# subway-timetable.net
KiCad netlist of a schematic drawn in EAGLE
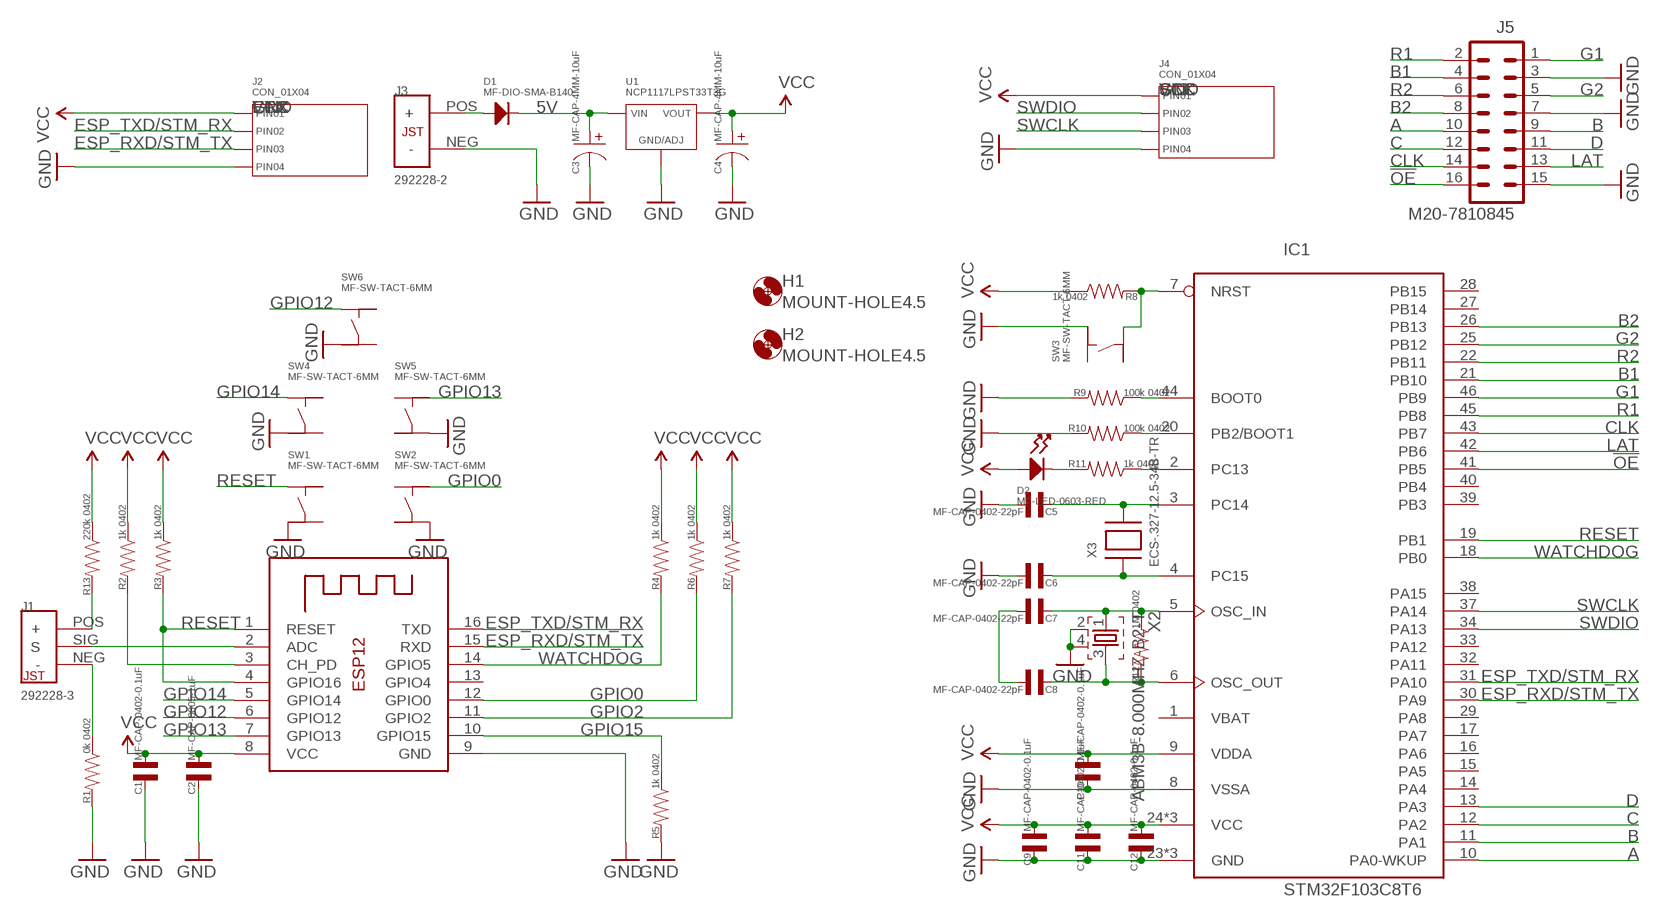
[diagram p0: schematic, sheet 1]

(export (version "E")
  (design (tool "Eeschema 10.0.6"))
  (components
    (comp (ref "C1")
      (value "MF-CAP-0402-0.1uF")
      (footprint "eagle-import:C0402")
      (libsource (lib "eagle-import") (part "CAPACITOR_NP_0402"))
    )
    (comp (ref "C2")
      (value "MF-CAP-0805-1uF")
      (footprint "eagle-import:C0805")
      (libsource (lib "eagle-import") (part "CAPACITOR_NP_0805"))
    )
    (comp (ref "C3")
      (value "MF-CAP-4MM-10uF")
      (footprint "eagle-import:CP4MM")
      (libsource (lib "eagle-import") (part "CAPACITOR_P_4MM"))
    )
    (comp (ref "C4")
      (value "MF-CAP-4MM-10uF")
      (footprint "eagle-import:CP4MM")
      (libsource (lib "eagle-import") (part "CAPACITOR_P_4MM"))
    )
    (comp (ref "C5")
      (value "MF-CAP-0402-22pF")
      (footprint "eagle-import:C0402")
      (libsource (lib "eagle-import") (part "CAPACITOR_NP_0402"))
    )
    (comp (ref "C6")
      (value "MF-CAP-0402-22pF")
      (footprint "eagle-import:C0402")
      (libsource (lib "eagle-import") (part "CAPACITOR_NP_0402"))
    )
    (comp (ref "C7")
      (value "MF-CAP-0402-22pF")
      (footprint "eagle-import:C0402")
      (libsource (lib "eagle-import") (part "CAPACITOR_NP_0402"))
    )
    (comp (ref "C8")
      (value "MF-CAP-0402-22pF")
      (footprint "eagle-import:C0402")
      (libsource (lib "eagle-import") (part "CAPACITOR_NP_0402"))
    )
    (comp (ref "C9")
      (value "MF-CAP-0402-0.1uF")
      (footprint "eagle-import:C0402")
      (libsource (lib "eagle-import") (part "CAPACITOR_NP_0402"))
    )
    (comp (ref "C10")
      (value "MF-CAP-0402-0.1uF")
      (footprint "eagle-import:C0402")
      (libsource (lib "eagle-import") (part "CAPACITOR_NP_0402"))
    )
    (comp (ref "C11")
      (value "MF-CAP-0402-0.1uF")
      (footprint "eagle-import:C0402")
      (libsource (lib "eagle-import") (part "CAPACITOR_NP_0402"))
    )
    (comp (ref "C12")
      (value "MF-CAP-0402-0.1uF")
      (footprint "eagle-import:C0402")
      (libsource (lib "eagle-import") (part "CAPACITOR_NP_0402"))
    )
    (comp (ref "D1")
      (value "MF-DIO-SMA-B140")
      (footprint "eagle-import:SMA")
      (fields (field (name "HOUSEPART") "YES"))
      (libsource (lib "eagle-import") (part "DIODES_SMA_B140"))
    )
    (comp (ref "D2")
      (value "MF-LED-0603-RED")
      (footprint "eagle-import:LED0603")
      (fields (field (name "HOUSEPART") "YES"))
      (libsource (lib "eagle-import") (part "LED_SINGLE-0603-RED"))
    )
    (comp (ref "H1")
      (value "MOUNT-HOLE4.5")
      (footprint "eagle-import:4,5")
      (libsource (lib "eagle-import") (part "MOUNT-HOLE4.5"))
    )
    (comp (ref "H2")
      (value "MOUNT-HOLE4.5")
      (footprint "eagle-import:4,5")
      (libsource (lib "eagle-import") (part "MOUNT-HOLE4.5"))
    )
    (comp (ref "IC1")
      (value "STM32F103C8T6")
      (footprint "eagle-import:LQFP48")
      (libsource (lib "eagle-import") (part "STM32F103CT8"))
    )
    (comp (ref "J1")
      (value "292228-3")
      (footprint "eagle-import:292228-3")
      (libsource (lib "eagle-import") (part "MINICT-3"))
    )
    (comp (ref "J2")
      (value "CON_01X04")
      (footprint "eagle-import:PTH_2.54MM_01X04_SPECIAL")
      (fields
        (field (name "LABEL01") "VCC")
        (field (name "LABEL02") "ETX")
        (field (name "LABEL03") "ERX")
        (field (name "LABEL04") "GND")
      )
      (libsource (lib "eagle-import") (part "CON_01X04"))
    )
    (comp (ref "J3")
      (value "292228-2")
      (footprint "eagle-import:292228-2")
      (libsource (lib "eagle-import") (part "MINICT"))
    )
    (comp (ref "J4")
      (value "CON_01X04")
      (footprint "eagle-import:PTH_2.54MM_01X04_SPECIAL")
      (fields
        (field (name "LABEL01") "VCC")
        (field (name "LABEL02") "SIO")
        (field (name "LABEL03") "SCK")
        (field (name "LABEL04") "GND")
      )
      (libsource (lib "eagle-import") (part "CON_01X04"))
    )
    (comp (ref "J5")
      (value "M20-7810845")
      (footprint "eagle-import:2X8_SMD")
      (libsource (lib "eagle-import") (part "M08X2SMD"))
    )
    (comp (ref "R1")
      (value "0k 0402")
      (footprint "eagle-import:R0402")
      (libsource (lib "eagle-import") (part "RESISTOR_0402"))
    )
    (comp (ref "R2")
      (value "1k 0402")
      (footprint "eagle-import:R0402")
      (libsource (lib "eagle-import") (part "RESISTOR_0402"))
    )
    (comp (ref "R3")
      (value "1k 0402")
      (footprint "eagle-import:R0402")
      (libsource (lib "eagle-import") (part "RESISTOR_0402"))
    )
    (comp (ref "R4")
      (value "1k 0402")
      (footprint "eagle-import:R0402")
      (libsource (lib "eagle-import") (part "RESISTOR_0402"))
    )
    (comp (ref "R5")
      (value "1k 0402")
      (footprint "eagle-import:R0402")
      (libsource (lib "eagle-import") (part "RESISTOR_0402"))
    )
    (comp (ref "R6")
      (value "1k 0402")
      (footprint "eagle-import:R0402")
      (libsource (lib "eagle-import") (part "RESISTOR_0402"))
    )
    (comp (ref "R7")
      (value "1k 0402")
      (footprint "eagle-import:R0402")
      (libsource (lib "eagle-import") (part "RESISTOR_0402"))
    )
    (comp (ref "R8")
      (value "1k 0402")
      (footprint "eagle-import:R0402")
      (libsource (lib "eagle-import") (part "RESISTOR_0402"))
    )
    (comp (ref "R9")
      (value "100k 0402")
      (footprint "eagle-import:R0402")
      (libsource (lib "eagle-import") (part "RESISTOR_0402"))
    )
    (comp (ref "R10")
      (value "100k 0402")
      (footprint "eagle-import:R0402")
      (libsource (lib "eagle-import") (part "RESISTOR_0402"))
    )
    (comp (ref "R11")
      (value "1k 0402")
      (footprint "eagle-import:R0402")
      (libsource (lib "eagle-import") (part "RESISTOR_0402"))
    )
    (comp (ref "R12")
      (value "1M 0402")
      (footprint "eagle-import:R0402")
      (libsource (lib "eagle-import") (part "RESISTOR_0402"))
    )
    (comp (ref "R13")
      (value "220k 0402")
      (footprint "eagle-import:R0402")
      (libsource (lib "eagle-import") (part "RESISTOR_0402"))
    )
    (comp (ref "SW1")
      (value "MF-SW-TACT-6MM")
      (footprint "eagle-import:TACT6MM")
      (fields (field (name "HOUSEPART") "YES"))
      (libsource (lib "eagle-import") (part "TACT_6MM"))
    )
    (comp (ref "SW2")
      (value "MF-SW-TACT-6MM")
      (footprint "eagle-import:TACT6MM")
      (fields (field (name "HOUSEPART") "YES"))
      (libsource (lib "eagle-import") (part "TACT_6MM"))
    )
    (comp (ref "SW3")
      (value "MF-SW-TACT-6MM")
      (footprint "eagle-import:TACT6MM")
      (fields (field (name "HOUSEPART") "YES"))
      (libsource (lib "eagle-import") (part "TACT_6MM"))
    )
    (comp (ref "SW4")
      (value "MF-SW-TACT-6MM")
      (footprint "eagle-import:TACT6MM")
      (fields (field (name "HOUSEPART") "YES"))
      (libsource (lib "eagle-import") (part "TACT_6MM"))
    )
    (comp (ref "SW5")
      (value "MF-SW-TACT-6MM")
      (footprint "eagle-import:TACT6MM")
      (fields (field (name "HOUSEPART") "YES"))
      (libsource (lib "eagle-import") (part "TACT_6MM"))
    )
    (comp (ref "SW6")
      (value "MF-SW-TACT-6MM")
      (footprint "eagle-import:TACT6MM")
      (fields (field (name "HOUSEPART") "YES"))
      (libsource (lib "eagle-import") (part "TACT_6MM"))
    )
    (comp (ref "U1")
      (value "NCP1117LPST33T3G")
      (footprint "eagle-import:SOT-223-3")
      (fields (field (name "HOUSEPART") "NO"))
      (libsource (lib "eagle-import") (part "NCP1117LPST33T3G"))
    )
    (comp (ref "X1")
      (value "ESP-12")
      (footprint "eagle-import:ESP-12")
      (libsource (lib "eagle-import") (part "ESP-12"))
    )
    (comp (ref "X2")
      (value "ABM3B-8.000MHZ-B2-T")
      (footprint "eagle-import:5.2X3.4-4-PAD")
      (libsource (lib "eagle-import") (part "CRYSTALS-GND-LID-CFPX-104"))
    )
    (comp (ref "X3")
      (value "ECS-.327-12.5-34B-TR")
      (footprint "eagle-import:XTAL3215")
      (libsource (lib "eagle-import") (part "XTAL-3.2X1.5"))
    )
  )
  (nets
    (net (code "1") (name "/5V") (class "Default")
      (node (ref "C3") (pin "P$1") (pinfunction "P$1_P$1") (pintype "passive"))
      (node (ref "D1") (pin "CATHODE") (pinfunction "CATHODE_CATHODE") (pintype "bidirectional"))
      (node (ref "U1") (pin "P$4") (pinfunction "VIN_P$4") (pintype "bidirectional"))
    )
    (net (code "2") (name "/A") (class "Default")
      (node (ref "IC1") (pin "10") (pinfunction "PA0-WKUP_10") (pintype "bidirectional"))
      (node (ref "J5") (pin "10") (pinfunction "10_10") (pintype "passive"))
    )
    (net (code "3") (name "/B") (class "Default")
      (node (ref "IC1") (pin "11") (pinfunction "PA1_11") (pintype "bidirectional"))
      (node (ref "J5") (pin "9") (pinfunction "9_9") (pintype "passive"))
    )
    (net (code "4") (name "/B1") (class "Default")
      (node (ref "IC1") (pin "21") (pinfunction "PB10_21") (pintype "bidirectional"))
      (node (ref "J5") (pin "4") (pinfunction "4_4") (pintype "passive"))
    )
    (net (code "5") (name "/B2") (class "Default")
      (node (ref "IC1") (pin "26") (pinfunction "PB13_26") (pintype "bidirectional"))
      (node (ref "J5") (pin "8") (pinfunction "8_8") (pintype "passive"))
    )
    (net (code "6") (name "/C") (class "Default")
      (node (ref "IC1") (pin "12") (pinfunction "PA2_12") (pintype "bidirectional"))
      (node (ref "J5") (pin "12") (pinfunction "12_12") (pintype "passive"))
    )
    (net (code "7") (name "/CLK") (class "Default")
      (node (ref "IC1") (pin "43") (pinfunction "PB7_43") (pintype "bidirectional"))
      (node (ref "J5") (pin "14") (pinfunction "14_14") (pintype "passive"))
    )
    (net (code "8") (name "/D") (class "Default")
      (node (ref "IC1") (pin "13") (pinfunction "PA3_13") (pintype "bidirectional"))
      (node (ref "J5") (pin "11") (pinfunction "11_11") (pintype "passive"))
    )
    (net (code "9") (name "/ESP_RXD{slash}STM_TX") (class "Default")
      (node (ref "IC1") (pin "30") (pinfunction "PA9_30") (pintype "bidirectional"))
      (node (ref "J2") (pin "P$3") (pinfunction "PIN3_P$3") (pintype "bidirectional"))
      (node (ref "X1") (pin "15") (pinfunction "RXD_15") (pintype "input"))
    )
    (net (code "10") (name "/ESP_TXD{slash}STM_RX") (class "Default")
      (node (ref "IC1") (pin "31") (pinfunction "PA10_31") (pintype "bidirectional"))
      (node (ref "J2") (pin "P$2") (pinfunction "PIN2_P$2") (pintype "bidirectional"))
      (node (ref "X1") (pin "16") (pinfunction "TXD_16") (pintype "output"))
    )
    (net (code "11") (name "/G1") (class "Default")
      (node (ref "IC1") (pin "46") (pinfunction "PB9_46") (pintype "bidirectional"))
      (node (ref "J5") (pin "1") (pinfunction "1_1") (pintype "passive"))
    )
    (net (code "12") (name "/G2") (class "Default")
      (node (ref "IC1") (pin "25") (pinfunction "PB12_25") (pintype "bidirectional"))
      (node (ref "J5") (pin "5") (pinfunction "5_5") (pintype "passive"))
    )
    (net (code "13") (name "/GPIO0") (class "Default")
      (node (ref "R6") (pin "P$2") (pinfunction "P$2_P$2") (pintype "passive"))
      (node (ref "SW2") (pin "P$2") (pinfunction "P$2_P$2") (pintype "bidirectional"))
      (node (ref "X1") (pin "12") (pinfunction "GPIO0_12") (pintype "bidirectional"))
    )
    (net (code "14") (name "/GPIO2") (class "Default")
      (node (ref "R7") (pin "P$2") (pinfunction "P$2_P$2") (pintype "passive"))
      (node (ref "X1") (pin "11") (pinfunction "GPIO2_11") (pintype "bidirectional"))
    )
    (net (code "15") (name "/GPIO12") (class "Default")
      (node (ref "SW6") (pin "P$1") (pinfunction "P$1_P$1") (pintype "bidirectional"))
      (node (ref "X1") (pin "6") (pinfunction "GPIO12_6") (pintype "bidirectional"))
    )
    (net (code "16") (name "/GPIO13") (class "Default")
      (node (ref "SW5") (pin "P$2") (pinfunction "P$2_P$2") (pintype "bidirectional"))
      (node (ref "X1") (pin "7") (pinfunction "GPIO13_7") (pintype "bidirectional"))
    )
    (net (code "17") (name "/GPIO14") (class "Default")
      (node (ref "SW4") (pin "P$1") (pinfunction "P$1_P$1") (pintype "bidirectional"))
      (node (ref "X1") (pin "5") (pinfunction "GPIO14_5") (pintype "bidirectional"))
    )
    (net (code "18") (name "/GPIO15") (class "Default")
      (node (ref "R5") (pin "P$1") (pinfunction "P$1_P$1") (pintype "passive"))
      (node (ref "X1") (pin "10") (pinfunction "GPIO15_10") (pintype "bidirectional"))
    )
    (net (code "19") (name "/LAT") (class "Default")
      (node (ref "IC1") (pin "42") (pinfunction "PB6_42") (pintype "bidirectional"))
      (node (ref "J5") (pin "13") (pinfunction "13_13") (pintype "passive"))
    )
    (net (code "20") (name "/R1") (class "Default")
      (node (ref "IC1") (pin "45") (pinfunction "PB8_45") (pintype "bidirectional"))
      (node (ref "J5") (pin "2") (pinfunction "2_2") (pintype "passive"))
    )
    (net (code "21") (name "/R2") (class "Default")
      (node (ref "IC1") (pin "22") (pinfunction "PB11_22") (pintype "bidirectional"))
      (node (ref "J5") (pin "6") (pinfunction "6_6") (pintype "passive"))
    )
    (net (code "22") (name "/RESET") (class "Default")
      (node (ref "IC1") (pin "19") (pinfunction "PB1_19") (pintype "bidirectional"))
      (node (ref "R3") (pin "P$2") (pinfunction "P$2_P$2") (pintype "passive"))
      (node (ref "SW1") (pin "P$1") (pinfunction "P$1_P$1") (pintype "bidirectional"))
      (node (ref "X1") (pin "1") (pinfunction "RESET_1") (pintype "input"))
      (node (ref "X1") (pin "4") (pinfunction "GPIO16_4") (pintype "bidirectional"))
    )
    (net (code "23") (name "/SWCLK") (class "Default")
      (node (ref "IC1") (pin "37") (pinfunction "PA14_37") (pintype "bidirectional"))
      (node (ref "J4") (pin "P$3") (pinfunction "PIN3_P$3") (pintype "bidirectional"))
    )
    (net (code "24") (name "/SWDIO") (class "Default")
      (node (ref "IC1") (pin "34") (pinfunction "PA13_34") (pintype "bidirectional"))
      (node (ref "J4") (pin "P$2") (pinfunction "PIN2_P$2") (pintype "bidirectional"))
    )
    (net (code "25") (name "/VBAT") (class "Default")
      (node (ref "IC1") (pin "1") (pinfunction "VBAT_1") (pintype "power_in"))
    )
    (net (code "26") (name "/WATCHDOG") (class "Default")
      (node (ref "IC1") (pin "18") (pinfunction "PB0_18") (pintype "bidirectional"))
      (node (ref "R4") (pin "P$2") (pinfunction "P$2_P$2") (pintype "passive"))
      (node (ref "X1") (pin "14") (pinfunction "GPIO5_14") (pintype "bidirectional"))
    )
    (net (code "27") (name "/~{OE}") (class "Default")
      (node (ref "IC1") (pin "41") (pinfunction "PB5_41") (pintype "bidirectional"))
      (node (ref "J5") (pin "16") (pinfunction "16_16") (pintype "passive"))
    )
    (net (code "28") (name "GND") (class "Default")
      (node (ref "C1") (pin "P$2") (pinfunction "P$2_P$2") (pintype "passive"))
      (node (ref "C10") (pin "P$2") (pinfunction "P$2_P$2") (pintype "passive"))
      (node (ref "C11") (pin "P$2") (pinfunction "P$2_P$2") (pintype "passive"))
      (node (ref "C12") (pin "P$2") (pinfunction "P$2_P$2") (pintype "passive"))
      (node (ref "C2") (pin "P$2") (pinfunction "P$2_P$2") (pintype "passive"))
      (node (ref "C3") (pin "P$2") (pinfunction "P$2_P$2") (pintype "passive"))
      (node (ref "C4") (pin "P$2") (pinfunction "P$2_P$2") (pintype "passive"))
      (node (ref "C5") (pin "P$1") (pinfunction "P$1_P$1") (pintype "passive"))
      (node (ref "C6") (pin "P$1") (pinfunction "P$1_P$1") (pintype "passive"))
      (node (ref "C9") (pin "P$2") (pinfunction "P$2_P$2") (pintype "passive"))
      (node (ref "IC1") (pin "23") (pinfunction "GND_23") (pintype "bidirectional"))
      (node (ref "IC1") (pin "35") (pinfunction "GND_35") (pintype "bidirectional"))
      (node (ref "IC1") (pin "47") (pinfunction "GND_47") (pintype "bidirectional"))
      (node (ref "IC1") (pin "8") (pinfunction "VSSA_8") (pintype "power_in"))
      (node (ref "J2") (pin "P$4") (pinfunction "PIN4_P$4") (pintype "bidirectional"))
      (node (ref "J3") (pin "NEG") (pinfunction "-_NEG") (pintype "bidirectional"))
      (node (ref "J4") (pin "P$4") (pinfunction "PIN4_P$4") (pintype "bidirectional"))
      (node (ref "J5") (pin "15") (pinfunction "15_15") (pintype "passive"))
      (node (ref "J5") (pin "3") (pinfunction "3_3") (pintype "passive"))
      (node (ref "J5") (pin "7") (pinfunction "7_7") (pintype "passive"))
      (node (ref "R1") (pin "P$2") (pinfunction "P$2_P$2") (pintype "passive"))
      (node (ref "R10") (pin "P$2") (pinfunction "P$2_P$2") (pintype "passive"))
      (node (ref "R5") (pin "P$2") (pinfunction "P$2_P$2") (pintype "passive"))
      (node (ref "R9") (pin "P$2") (pinfunction "P$2_P$2") (pintype "passive"))
      (node (ref "SW1") (pin "P$3") (pinfunction "P$3_P$3") (pintype "bidirectional"))
      (node (ref "SW2") (pin "P$4") (pinfunction "P$4_P$4") (pintype "bidirectional"))
      (node (ref "SW3") (pin "P$2") (pinfunction "P$2_P$2") (pintype "bidirectional"))
      (node (ref "SW4") (pin "P$3") (pinfunction "P$3_P$3") (pintype "bidirectional"))
      (node (ref "SW5") (pin "P$4") (pinfunction "P$4_P$4") (pintype "bidirectional"))
      (node (ref "SW6") (pin "P$3") (pinfunction "P$3_P$3") (pintype "bidirectional"))
      (node (ref "U1") (pin "P$2") (pinfunction "GND/ADJ_P$2") (pintype "bidirectional"))
      (node (ref "X1") (pin "9") (pinfunction "GND_9") (pintype "power_in"))
      (node (ref "X2") (pin "2") (pinfunction "2_2") (pintype "passive"))
      (node (ref "X2") (pin "4") (pinfunction "4_4") (pintype "passive"))
    )
    (net (code "29") (name "Net-(C7-PadP$1)") (class "Default")
      (node (ref "C7") (pin "P$1") (pinfunction "P$1_P$1") (pintype "passive"))
      (node (ref "C8") (pin "P$1") (pinfunction "P$1_P$1") (pintype "passive"))
    )
    (net (code "30") (name "Net-(D2-PadCATHODE)") (class "Default")
      (node (ref "D2") (pin "CATHODE") (pinfunction "CATHODE_CATHODE") (pintype "power_in"))
      (node (ref "R11") (pin "P$2") (pinfunction "P$2_P$2") (pintype "passive"))
    )
    (net (code "31") (name "Net-(IC1-BOOT0)") (class "Default")
      (node (ref "IC1") (pin "44") (pinfunction "BOOT0_44") (pintype "input"))
      (node (ref "R9") (pin "P$1") (pinfunction "P$1_P$1") (pintype "passive"))
    )
    (net (code "32") (name "Net-(IC1-NRST)") (class "Default")
      (node (ref "IC1") (pin "7") (pinfunction "NRST_7") (pintype "bidirectional"))
      (node (ref "R8") (pin "P$2") (pinfunction "P$2_P$2") (pintype "passive"))
      (node (ref "SW3") (pin "P$4") (pinfunction "P$4_P$4") (pintype "bidirectional"))
    )
    (net (code "33") (name "Net-(IC1-OSC_IN)") (class "Default")
      (node (ref "C7") (pin "P$2") (pinfunction "P$2_P$2") (pintype "passive"))
      (node (ref "IC1") (pin "5") (pinfunction "OSC_IN_5") (pintype "bidirectional"))
      (node (ref "R12") (pin "P$1") (pinfunction "P$1_P$1") (pintype "passive"))
      (node (ref "X2") (pin "1") (pinfunction "1_1") (pintype "passive"))
    )
    (net (code "34") (name "Net-(IC1-OSC_OUT)") (class "Default")
      (node (ref "C8") (pin "P$2") (pinfunction "P$2_P$2") (pintype "passive"))
      (node (ref "IC1") (pin "6") (pinfunction "OSC_OUT_6") (pintype "bidirectional"))
      (node (ref "R12") (pin "P$2") (pinfunction "P$2_P$2") (pintype "passive"))
      (node (ref "X2") (pin "3") (pinfunction "3_3") (pintype "passive"))
    )
    (net (code "35") (name "Net-(IC1-PB2{slash}BOOT1)") (class "Default")
      (node (ref "IC1") (pin "20") (pinfunction "PB2/BOOT1_20") (pintype "bidirectional"))
      (node (ref "R10") (pin "P$1") (pinfunction "P$1_P$1") (pintype "passive"))
    )
    (net (code "36") (name "Net-(IC1-PC13)") (class "Default")
      (node (ref "IC1") (pin "2") (pinfunction "PC13_2") (pintype "bidirectional"))
      (node (ref "R11") (pin "P$1") (pinfunction "P$1_P$1") (pintype "passive"))
    )
    (net (code "37") (name "Net-(IC1-PC14)") (class "Default")
      (node (ref "C5") (pin "P$2") (pinfunction "P$2_P$2") (pintype "passive"))
      (node (ref "IC1") (pin "3") (pinfunction "PC14_3") (pintype "bidirectional"))
      (node (ref "X3") (pin "P$2") (pinfunction "P$2_P$2") (pintype "bidirectional"))
    )
    (net (code "38") (name "Net-(IC1-PC15)") (class "Default")
      (node (ref "C6") (pin "P$2") (pinfunction "P$2_P$2") (pintype "passive"))
      (node (ref "IC1") (pin "4") (pinfunction "PC15_4") (pintype "bidirectional"))
      (node (ref "X3") (pin "P$1") (pinfunction "P$1_P$1") (pintype "bidirectional"))
    )
    (net (code "39") (name "Net-(J1-+)") (class "Default")
      (node (ref "J1") (pin "POS") (pinfunction "+_POS") (pintype "bidirectional"))
      (node (ref "R13") (pin "P$2") (pinfunction "P$2_P$2") (pintype "passive"))
    )
    (net (code "40") (name "Net-(J1--)") (class "Default")
      (node (ref "J1") (pin "NEG") (pinfunction "-_NEG") (pintype "bidirectional"))
      (node (ref "R1") (pin "P$1") (pinfunction "P$1_P$1") (pintype "passive"))
    )
    (net (code "41") (name "Net-(J1-S)") (class "Default")
      (node (ref "J1") (pin "SIG") (pinfunction "S_SIG") (pintype "bidirectional"))
      (node (ref "X1") (pin "2") (pinfunction "ADC_2") (pintype "passive"))
    )
    (net (code "42") (name "Net-(J3-+)") (class "Default")
      (node (ref "D1") (pin "ANODE") (pinfunction "ANODE_ANODE") (pintype "bidirectional"))
      (node (ref "J3") (pin "POS") (pinfunction "+_POS") (pintype "bidirectional"))
    )
    (net (code "43") (name "Net-(X1-CH_PD)") (class "Default")
      (node (ref "R2") (pin "P$2") (pinfunction "P$2_P$2") (pintype "passive"))
      (node (ref "X1") (pin "3") (pinfunction "CH_PD_3") (pintype "input"))
    )
    (net (code "44") (name "VCC") (class "Default")
      (node (ref "C1") (pin "P$1") (pinfunction "P$1_P$1") (pintype "passive"))
      (node (ref "C10") (pin "P$1") (pinfunction "P$1_P$1") (pintype "passive"))
      (node (ref "C11") (pin "P$1") (pinfunction "P$1_P$1") (pintype "passive"))
      (node (ref "C12") (pin "P$1") (pinfunction "P$1_P$1") (pintype "passive"))
      (node (ref "C2") (pin "P$1") (pinfunction "P$1_P$1") (pintype "passive"))
      (node (ref "C4") (pin "P$1") (pinfunction "P$1_P$1") (pintype "passive"))
      (node (ref "C9") (pin "P$1") (pinfunction "P$1_P$1") (pintype "passive"))
      (node (ref "D2") (pin "ANODE") (pinfunction "ANODE_ANODE") (pintype "power_in"))
      (node (ref "IC1") (pin "24") (pinfunction "VCC_24") (pintype "bidirectional"))
      (node (ref "IC1") (pin "36") (pinfunction "VCC_36") (pintype "bidirectional"))
      (node (ref "IC1") (pin "48") (pinfunction "VCC_48") (pintype "bidirectional"))
      (node (ref "IC1") (pin "9") (pinfunction "VDDA_9") (pintype "power_in"))
      (node (ref "J2") (pin "P$1") (pinfunction "PIN1_P$1") (pintype "bidirectional"))
      (node (ref "J4") (pin "P$1") (pinfunction "PIN1_P$1") (pintype "bidirectional"))
      (node (ref "R13") (pin "P$1") (pinfunction "P$1_P$1") (pintype "passive"))
      (node (ref "R2") (pin "P$1") (pinfunction "P$1_P$1") (pintype "passive"))
      (node (ref "R3") (pin "P$1") (pinfunction "P$1_P$1") (pintype "passive"))
      (node (ref "R4") (pin "P$1") (pinfunction "P$1_P$1") (pintype "passive"))
      (node (ref "R6") (pin "P$1") (pinfunction "P$1_P$1") (pintype "passive"))
      (node (ref "R7") (pin "P$1") (pinfunction "P$1_P$1") (pintype "passive"))
      (node (ref "R8") (pin "P$1") (pinfunction "P$1_P$1") (pintype "passive"))
      (node (ref "U1") (pin "P$1") (pinfunction "VOUT_P$1") (pintype "bidirectional"))
      (node (ref "U1") (pin "P$3") (pinfunction "VOUT_P$3") (pintype "bidirectional"))
      (node (ref "X1") (pin "8") (pinfunction "VCC_8") (pintype "power_in"))
    )
    (net (code "45") (name "unconnected-(IC1-PA4-Pad14)") (class "Default")
      (node (ref "IC1") (pin "14") (pinfunction "PA4_14") (pintype "bidirectional"))
    )
    (net (code "46") (name "unconnected-(IC1-PA5-Pad15)") (class "Default")
      (node (ref "IC1") (pin "15") (pinfunction "PA5_15") (pintype "bidirectional"))
    )
    (net (code "47") (name "unconnected-(IC1-PA6-Pad16)") (class "Default")
      (node (ref "IC1") (pin "16") (pinfunction "PA6_16") (pintype "bidirectional"))
    )
    (net (code "48") (name "unconnected-(IC1-PA7-Pad17)") (class "Default")
      (node (ref "IC1") (pin "17") (pinfunction "PA7_17") (pintype "bidirectional"))
    )
    (net (code "49") (name "unconnected-(IC1-PA8-Pad29)") (class "Default")
      (node (ref "IC1") (pin "29") (pinfunction "PA8_29") (pintype "bidirectional"))
    )
    (net (code "50") (name "unconnected-(IC1-PA11-Pad32)") (class "Default")
      (node (ref "IC1") (pin "32") (pinfunction "PA11_32") (pintype "bidirectional"))
    )
    (net (code "51") (name "unconnected-(IC1-PA12-Pad33)") (class "Default")
      (node (ref "IC1") (pin "33") (pinfunction "PA12_33") (pintype "bidirectional"))
    )
    (net (code "52") (name "unconnected-(IC1-PA15-Pad38)") (class "Default")
      (node (ref "IC1") (pin "38") (pinfunction "PA15_38") (pintype "bidirectional"))
    )
    (net (code "53") (name "unconnected-(IC1-PB3-Pad39)") (class "Default")
      (node (ref "IC1") (pin "39") (pinfunction "PB3_39") (pintype "bidirectional"))
    )
    (net (code "54") (name "unconnected-(IC1-PB4-Pad40)") (class "Default")
      (node (ref "IC1") (pin "40") (pinfunction "PB4_40") (pintype "bidirectional"))
    )
    (net (code "55") (name "unconnected-(IC1-PB14-Pad27)") (class "Default")
      (node (ref "IC1") (pin "27") (pinfunction "PB14_27") (pintype "bidirectional"))
    )
    (net (code "56") (name "unconnected-(IC1-PB15-Pad28)") (class "Default")
      (node (ref "IC1") (pin "28") (pinfunction "PB15_28") (pintype "bidirectional"))
    )
    (net (code "57") (name "unconnected-(SW1-PadP$2)") (class "Default")
      (node (ref "SW1") (pin "P$2") (pinfunction "P$2_P$2") (pintype "bidirectional"))
    )
    (net (code "58") (name "unconnected-(SW1-PadP$4)") (class "Default")
      (node (ref "SW1") (pin "P$4") (pinfunction "P$4_P$4") (pintype "bidirectional"))
    )
    (net (code "59") (name "unconnected-(SW2-PadP$1)") (class "Default")
      (node (ref "SW2") (pin "P$1") (pinfunction "P$1_P$1") (pintype "bidirectional"))
    )
    (net (code "60") (name "unconnected-(SW2-PadP$3)") (class "Default")
      (node (ref "SW2") (pin "P$3") (pinfunction "P$3_P$3") (pintype "bidirectional"))
    )
    (net (code "61") (name "unconnected-(SW3-PadP$1)") (class "Default")
      (node (ref "SW3") (pin "P$1") (pinfunction "P$1_P$1") (pintype "bidirectional"))
    )
    (net (code "62") (name "unconnected-(SW3-PadP$3)") (class "Default")
      (node (ref "SW3") (pin "P$3") (pinfunction "P$3_P$3") (pintype "bidirectional"))
    )
    (net (code "63") (name "unconnected-(SW4-PadP$2)") (class "Default")
      (node (ref "SW4") (pin "P$2") (pinfunction "P$2_P$2") (pintype "bidirectional"))
    )
    (net (code "64") (name "unconnected-(SW4-PadP$4)") (class "Default")
      (node (ref "SW4") (pin "P$4") (pinfunction "P$4_P$4") (pintype "bidirectional"))
    )
    (net (code "65") (name "unconnected-(SW5-PadP$1)") (class "Default")
      (node (ref "SW5") (pin "P$1") (pinfunction "P$1_P$1") (pintype "bidirectional"))
    )
    (net (code "66") (name "unconnected-(SW5-PadP$3)") (class "Default")
      (node (ref "SW5") (pin "P$3") (pinfunction "P$3_P$3") (pintype "bidirectional"))
    )
    (net (code "67") (name "unconnected-(SW6-PadP$2)") (class "Default")
      (node (ref "SW6") (pin "P$2") (pinfunction "P$2_P$2") (pintype "bidirectional"))
    )
    (net (code "68") (name "unconnected-(SW6-PadP$4)") (class "Default")
      (node (ref "SW6") (pin "P$4") (pinfunction "P$4_P$4") (pintype "bidirectional"))
    )
    (net (code "69") (name "unconnected-(X1-GPIO4-Pad13)") (class "Default")
      (node (ref "X1") (pin "13") (pinfunction "GPIO4_13") (pintype "bidirectional"))
    )
  )
)
